# LEDS_-_Status.net
KiCad netlist of a schematic drawn in Altium Designer
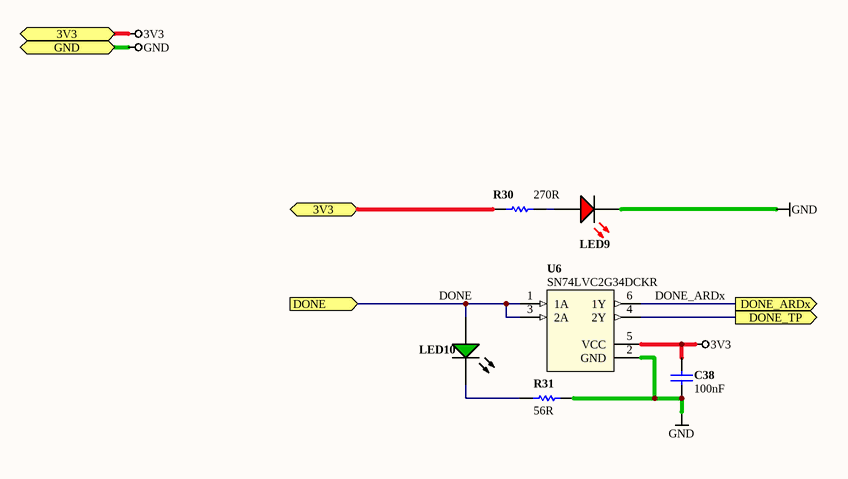
[diagram p0: LEDS - Status.SchDoc]

(export (version "E")
  (design (tool "Eeschema 10.0.6"))
  (components
    (comp (ref "C38")
      (value "100nF")
      (footprint "CAPC0402(1005)60_L")
      (description "CAP 100nF 10V ±5% 0402 (1005 Metric) Thickness 0.6mm SMD")
      (fields (field (name "TOLERANCE") "±5%") (field (name "MANUFACTURER PART NUMBER") "C0402C104K8PACTU"))
      (libsource (lib "Altium Content Vault") (part "CMP-1034-02064-1"))
    )
    (comp (ref "LED9")
      (value "0402-LED-RED")
      (footprint "LED_0402")
      (description "0402 LED,RED")
      (fields (field (name "MANUFACTURER PART NUMBER") "LTST-C190KRKT"))
      (libsource (lib "Component_DB") (part "LED_RED_A1K2-2"))
    )
    (comp (ref "LED10")
      (value "LED_GREEN_APT1608SGC")
      (footprint "LED0603")
      (description "SMD 0603 LED, GREEN")
      (fields (field (name "PARTNUMBER") "APT1608SGC"))
      (libsource (lib "LED-GREEN-APT1608SGC") (part "LED_GREEN_APT1608SGC"))
    )
    (comp (ref "R30")
      (value "270R")
      (footprint "RESC0402(1005)40_L")
      (description "0402 (1005 Metric) 1/16 W 270R 1 Thick Film Chip Resistor")
      (fields (field (name "POWER") "1/16 W") (field (name "MANUFACTURER PART NUMBER") "RC1005F271CS"))
      (libsource (lib "Component_DB") (part "RES"))
    )
    (comp (ref "R31")
      (value "56R")
      (footprint "RESC0402(1005)_L")
      (description "56R 0.063W 1% 0402 (1005 Metric)  SMD")
      (fields (field (name "POWER") "0.063 W") (field (name "TOLERANCE") "1 %"))
      (libsource (lib "Altium Content Vault") (part "CMP-1011-00369-1"))
    )
    (comp (ref "U6")
      (value "SN74LVC2G34DCKR")
      (footprint "TI-DCK6_L")
      (description "IC BUFFER DUAL NON-INV SC706")
      (fields (field (name "MANUFACTURER") "Texas Instruments"))
      (libsource (lib "Component_Database") (part "SN74LVC2G34"))
    )
  )
  (nets
    (net (code "1") (name "/DONE") (class "Default")
      (node (ref "LED10") (pin "1") (pinfunction "A_1") (pintype "passive"))
      (node (ref "U6") (pin "1") (pinfunction "1A_1") (pintype "input"))
      (node (ref "U6") (pin "3") (pinfunction "2A_3") (pintype "input"))
    )
    (net (code "2") (name "/DONE_ARDx") (class "Default")
      (node (ref "U6") (pin "6") (pinfunction "1Y_6") (pintype "output"))
    )
    (net (code "3") (name "/DONE_TP") (class "Default")
      (node (ref "U6") (pin "4") (pinfunction "2Y_4") (pintype "output"))
    )
    (net (code "4") (name "3V3") (class "Default")
      (node (ref "C38") (pin "2") (pinfunction "2_2") (pintype "passive"))
      (node (ref "R30") (pin "1") (pinfunction "1_1") (pintype "passive"))
      (node (ref "U6") (pin "5") (pinfunction "VCC_5") (pintype "power_in"))
    )
    (net (code "5") (name "GND") (class "Default")
      (node (ref "C38") (pin "1") (pinfunction "1_1") (pintype "passive"))
      (node (ref "LED9") (pin "2") (pinfunction "K_2") (pintype "passive"))
      (node (ref "R31") (pin "2") (pinfunction "2_2") (pintype "passive"))
      (node (ref "U6") (pin "2") (pinfunction "GND_2") (pintype "power_in"))
    )
    (net (code "6") (name "Net-(LED9-A)") (class "Default")
      (node (ref "LED9") (pin "1") (pinfunction "A_1") (pintype "passive"))
      (node (ref "R30") (pin "2") (pinfunction "2_2") (pintype "passive"))
    )
    (net (code "7") (name "Net-(LED10-K)") (class "Default")
      (node (ref "LED10") (pin "2") (pinfunction "K_2") (pintype "passive"))
      (node (ref "R31") (pin "1") (pinfunction "1_1") (pintype "passive"))
    )
  )
)
